# Sheet2.net
KiCad netlist of a schematic drawn in Altium Designer
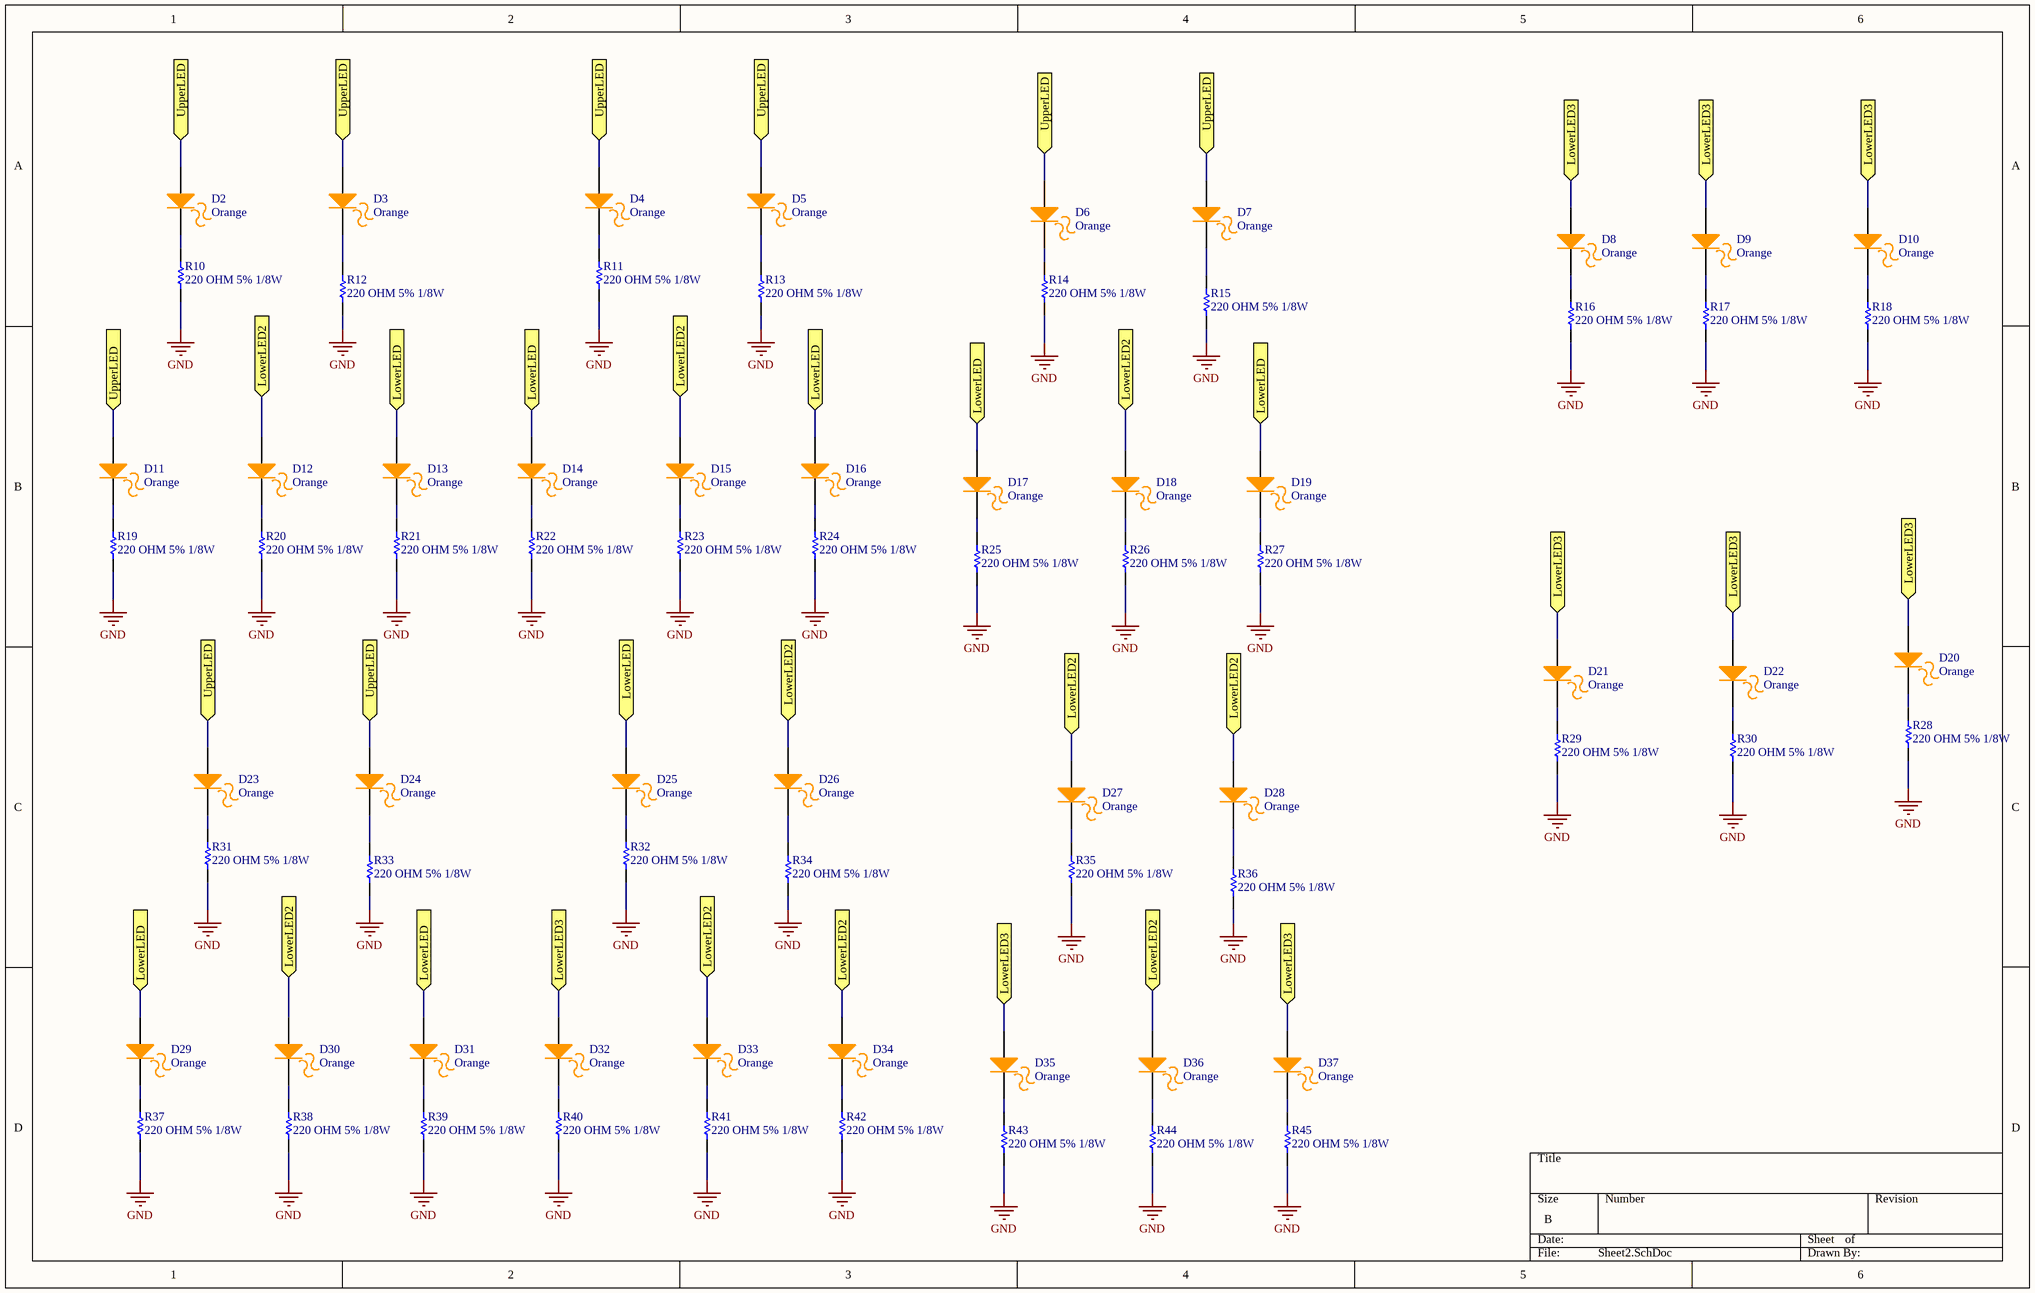
[diagram p0: Sheet2.SchDoc]

(export (version "E")
  (design (tool "Eeschema 10.0.6"))
  (components
    (comp (ref "D2")
      (value "Orange")
      (footprint "0603 LED Green")
      (description "LED ORANGE CLEAR SMD")
      (fields (field (name "MANUFACTURER") "Lite-On Inc."))
      (libsource (lib "CircuitStudioSchematic.Lib") (part "LTST-C191KFKT"))
    )
    (comp (ref "D3")
      (value "Orange")
      (footprint "0603 LED Green")
      (description "LED ORANGE CLEAR SMD")
      (fields (field (name "MANUFACTURER") "Lite-On Inc."))
      (libsource (lib "CircuitStudioSchematic.Lib") (part "LTST-C191KFKT"))
    )
    (comp (ref "D4")
      (value "Orange")
      (footprint "0603 LED Green")
      (description "LED ORANGE CLEAR SMD")
      (fields (field (name "MANUFACTURER") "Lite-On Inc."))
      (libsource (lib "CircuitStudioSchematic.Lib") (part "LTST-C191KFKT"))
    )
    (comp (ref "D5")
      (value "Orange")
      (footprint "0603 LED Green")
      (description "LED ORANGE CLEAR SMD")
      (fields (field (name "MANUFACTURER") "Lite-On Inc."))
      (libsource (lib "CircuitStudioSchematic.Lib") (part "LTST-C191KFKT"))
    )
    (comp (ref "D6")
      (value "Orange")
      (footprint "0603 LED Green")
      (description "LED ORANGE CLEAR SMD")
      (fields (field (name "MANUFACTURER") "Lite-On Inc."))
      (libsource (lib "CircuitStudioSchematic.Lib") (part "LTST-C191KFKT"))
    )
    (comp (ref "D7")
      (value "Orange")
      (footprint "0603 LED Green")
      (description "LED ORANGE CLEAR SMD")
      (fields (field (name "MANUFACTURER") "Lite-On Inc."))
      (libsource (lib "CircuitStudioSchematic.Lib") (part "LTST-C191KFKT"))
    )
    (comp (ref "D8")
      (value "Orange")
      (footprint "0603 LED Green")
      (description "LED ORANGE CLEAR SMD")
      (fields (field (name "MANUFACTURER") "Lite-On Inc."))
      (libsource (lib "CircuitStudioSchematic.Lib") (part "LTST-C191KFKT"))
    )
    (comp (ref "D9")
      (value "Orange")
      (footprint "0603 LED Green")
      (description "LED ORANGE CLEAR SMD")
      (fields (field (name "MANUFACTURER") "Lite-On Inc."))
      (libsource (lib "CircuitStudioSchematic.Lib") (part "LTST-C191KFKT"))
    )
    (comp (ref "D10")
      (value "Orange")
      (footprint "0603 LED Green")
      (description "LED ORANGE CLEAR SMD")
      (fields (field (name "MANUFACTURER") "Lite-On Inc."))
      (libsource (lib "CircuitStudioSchematic.Lib") (part "LTST-C191KFKT"))
    )
    (comp (ref "D11")
      (value "Orange")
      (footprint "0603 LED Green")
      (description "LED ORANGE CLEAR SMD")
      (fields (field (name "MANUFACTURER") "Lite-On Inc."))
      (libsource (lib "CircuitStudioSchematic.Lib") (part "LTST-C191KFKT"))
    )
    (comp (ref "D12")
      (value "Orange")
      (footprint "0603 LED Green")
      (description "LED ORANGE CLEAR SMD")
      (fields (field (name "MANUFACTURER") "Lite-On Inc."))
      (libsource (lib "CircuitStudioSchematic.Lib") (part "LTST-C191KFKT"))
    )
    (comp (ref "D13")
      (value "Orange")
      (footprint "0603 LED Green")
      (description "LED ORANGE CLEAR SMD")
      (fields (field (name "MANUFACTURER") "Lite-On Inc."))
      (libsource (lib "CircuitStudioSchematic.Lib") (part "LTST-C191KFKT"))
    )
    (comp (ref "D14")
      (value "Orange")
      (footprint "0603 LED Green")
      (description "LED ORANGE CLEAR SMD")
      (fields (field (name "MANUFACTURER") "Lite-On Inc."))
      (libsource (lib "CircuitStudioSchematic.Lib") (part "LTST-C191KFKT"))
    )
    (comp (ref "D15")
      (value "Orange")
      (footprint "0603 LED Green")
      (description "LED ORANGE CLEAR SMD")
      (fields (field (name "MANUFACTURER") "Lite-On Inc."))
      (libsource (lib "CircuitStudioSchematic.Lib") (part "LTST-C191KFKT"))
    )
    (comp (ref "D16")
      (value "Orange")
      (footprint "0603 LED Green")
      (description "LED ORANGE CLEAR SMD")
      (fields (field (name "MANUFACTURER") "Lite-On Inc."))
      (libsource (lib "CircuitStudioSchematic.Lib") (part "LTST-C191KFKT"))
    )
    (comp (ref "D17")
      (value "Orange")
      (footprint "0603 LED Green")
      (description "LED ORANGE CLEAR SMD")
      (fields (field (name "MANUFACTURER") "Lite-On Inc."))
      (libsource (lib "CircuitStudioSchematic.Lib") (part "LTST-C191KFKT"))
    )
    (comp (ref "D18")
      (value "Orange")
      (footprint "0603 LED Green")
      (description "LED ORANGE CLEAR SMD")
      (fields (field (name "MANUFACTURER") "Lite-On Inc."))
      (libsource (lib "CircuitStudioSchematic.Lib") (part "LTST-C191KFKT"))
    )
    (comp (ref "D19")
      (value "Orange")
      (footprint "0603 LED Green")
      (description "LED ORANGE CLEAR SMD")
      (fields (field (name "MANUFACTURER") "Lite-On Inc."))
      (libsource (lib "CircuitStudioSchematic.Lib") (part "LTST-C191KFKT"))
    )
    (comp (ref "D20")
      (value "Orange")
      (footprint "0603 LED Green")
      (description "LED ORANGE CLEAR SMD")
      (fields (field (name "MANUFACTURER") "Lite-On Inc."))
      (libsource (lib "CircuitStudioSchematic.Lib") (part "LTST-C191KFKT"))
    )
    (comp (ref "D21")
      (value "Orange")
      (footprint "0603 LED Green")
      (description "LED ORANGE CLEAR SMD")
      (fields (field (name "MANUFACTURER") "Lite-On Inc."))
      (libsource (lib "CircuitStudioSchematic.Lib") (part "LTST-C191KFKT"))
    )
    (comp (ref "D22")
      (value "Orange")
      (footprint "0603 LED Green")
      (description "LED ORANGE CLEAR SMD")
      (fields (field (name "MANUFACTURER") "Lite-On Inc."))
      (libsource (lib "CircuitStudioSchematic.Lib") (part "LTST-C191KFKT"))
    )
    (comp (ref "D23")
      (value "Orange")
      (footprint "0603 LED Green")
      (description "LED ORANGE CLEAR SMD")
      (fields (field (name "MANUFACTURER") "Lite-On Inc."))
      (libsource (lib "CircuitStudioSchematic.Lib") (part "LTST-C191KFKT"))
    )
    (comp (ref "D24")
      (value "Orange")
      (footprint "0603 LED Green")
      (description "LED ORANGE CLEAR SMD")
      (fields (field (name "MANUFACTURER") "Lite-On Inc."))
      (libsource (lib "CircuitStudioSchematic.Lib") (part "LTST-C191KFKT"))
    )
    (comp (ref "D25")
      (value "Orange")
      (footprint "0603 LED Green")
      (description "LED ORANGE CLEAR SMD")
      (fields (field (name "MANUFACTURER") "Lite-On Inc."))
      (libsource (lib "CircuitStudioSchematic.Lib") (part "LTST-C191KFKT"))
    )
    (comp (ref "D26")
      (value "Orange")
      (footprint "0603 LED Green")
      (description "LED ORANGE CLEAR SMD")
      (fields (field (name "MANUFACTURER") "Lite-On Inc."))
      (libsource (lib "CircuitStudioSchematic.Lib") (part "LTST-C191KFKT"))
    )
    (comp (ref "D27")
      (value "Orange")
      (footprint "0603 LED Green")
      (description "LED ORANGE CLEAR SMD")
      (fields (field (name "MANUFACTURER") "Lite-On Inc."))
      (libsource (lib "CircuitStudioSchematic.Lib") (part "LTST-C191KFKT"))
    )
    (comp (ref "D28")
      (value "Orange")
      (footprint "0603 LED Green")
      (description "LED ORANGE CLEAR SMD")
      (fields (field (name "MANUFACTURER") "Lite-On Inc."))
      (libsource (lib "CircuitStudioSchematic.Lib") (part "LTST-C191KFKT"))
    )
    (comp (ref "D29")
      (value "Orange")
      (footprint "0603 LED Green")
      (description "LED ORANGE CLEAR SMD")
      (fields (field (name "MANUFACTURER") "Lite-On Inc."))
      (libsource (lib "CircuitStudioSchematic.Lib") (part "LTST-C191KFKT"))
    )
    (comp (ref "D30")
      (value "Orange")
      (footprint "0603 LED Green")
      (description "LED ORANGE CLEAR SMD")
      (fields (field (name "MANUFACTURER") "Lite-On Inc."))
      (libsource (lib "CircuitStudioSchematic.Lib") (part "LTST-C191KFKT"))
    )
    (comp (ref "D31")
      (value "Orange")
      (footprint "0603 LED Green")
      (description "LED ORANGE CLEAR SMD")
      (fields (field (name "MANUFACTURER") "Lite-On Inc."))
      (libsource (lib "CircuitStudioSchematic.Lib") (part "LTST-C191KFKT"))
    )
    (comp (ref "D32")
      (value "Orange")
      (footprint "0603 LED Green")
      (description "LED ORANGE CLEAR SMD")
      (fields (field (name "MANUFACTURER") "Lite-On Inc."))
      (libsource (lib "CircuitStudioSchematic.Lib") (part "LTST-C191KFKT"))
    )
    (comp (ref "D33")
      (value "Orange")
      (footprint "0603 LED Green")
      (description "LED ORANGE CLEAR SMD")
      (fields (field (name "MANUFACTURER") "Lite-On Inc."))
      (libsource (lib "CircuitStudioSchematic.Lib") (part "LTST-C191KFKT"))
    )
    (comp (ref "D34")
      (value "Orange")
      (footprint "0603 LED Green")
      (description "LED ORANGE CLEAR SMD")
      (fields (field (name "MANUFACTURER") "Lite-On Inc."))
      (libsource (lib "CircuitStudioSchematic.Lib") (part "LTST-C191KFKT"))
    )
    (comp (ref "D35")
      (value "Orange")
      (footprint "0603 LED Green")
      (description "LED ORANGE CLEAR SMD")
      (fields (field (name "MANUFACTURER") "Lite-On Inc."))
      (libsource (lib "CircuitStudioSchematic.Lib") (part "LTST-C191KFKT"))
    )
    (comp (ref "D36")
      (value "Orange")
      (footprint "0603 LED Green")
      (description "LED ORANGE CLEAR SMD")
      (fields (field (name "MANUFACTURER") "Lite-On Inc."))
      (libsource (lib "CircuitStudioSchematic.Lib") (part "LTST-C191KFKT"))
    )
    (comp (ref "D37")
      (value "Orange")
      (footprint "0603 LED Green")
      (description "LED ORANGE CLEAR SMD")
      (fields (field (name "MANUFACTURER") "Lite-On Inc."))
      (libsource (lib "CircuitStudioSchematic.Lib") (part "LTST-C191KFKT"))
    )
    (comp (ref "R10")
      (value "220 OHM 5% 1/8W")
      (footprint "SMD-0805-RES")
      (description "RES SMD 220 OHM 5% 1/8W 0805")
      (fields (field (name "MANUFACTURER") "Yageo"))
      (libsource (lib "CircuitStudioSchematic.Lib") (part "RC0805JR-07220RL"))
    )
    (comp (ref "R11")
      (value "220 OHM 5% 1/8W")
      (footprint "SMD-0805-RES")
      (description "RES SMD 220 OHM 5% 1/8W 0805")
      (fields (field (name "MANUFACTURER") "Yageo"))
      (libsource (lib "CircuitStudioSchematic.Lib") (part "RC0805JR-07220RL"))
    )
    (comp (ref "R12")
      (value "220 OHM 5% 1/8W")
      (footprint "SMD-0805-RES")
      (description "RES SMD 220 OHM 5% 1/8W 0805")
      (fields (field (name "MANUFACTURER") "Yageo"))
      (libsource (lib "CircuitStudioSchematic.Lib") (part "RC0805JR-07220RL"))
    )
    (comp (ref "R13")
      (value "220 OHM 5% 1/8W")
      (footprint "SMD-0805-RES")
      (description "RES SMD 220 OHM 5% 1/8W 0805")
      (fields (field (name "MANUFACTURER") "Yageo"))
      (libsource (lib "CircuitStudioSchematic.Lib") (part "RC0805JR-07220RL"))
    )
    (comp (ref "R14")
      (value "220 OHM 5% 1/8W")
      (footprint "SMD-0805-RES")
      (description "RES SMD 220 OHM 5% 1/8W 0805")
      (fields (field (name "MANUFACTURER") "Yageo"))
      (libsource (lib "CircuitStudioSchematic.Lib") (part "RC0805JR-07220RL"))
    )
    (comp (ref "R15")
      (value "220 OHM 5% 1/8W")
      (footprint "SMD-0805-RES")
      (description "RES SMD 220 OHM 5% 1/8W 0805")
      (fields (field (name "MANUFACTURER") "Yageo"))
      (libsource (lib "CircuitStudioSchematic.Lib") (part "RC0805JR-07220RL"))
    )
    (comp (ref "R16")
      (value "220 OHM 5% 1/8W")
      (footprint "SMD-0805-RES")
      (description "RES SMD 220 OHM 5% 1/8W 0805")
      (fields (field (name "MANUFACTURER") "Yageo"))
      (libsource (lib "CircuitStudioSchematic.Lib") (part "RC0805JR-07220RL"))
    )
    (comp (ref "R17")
      (value "220 OHM 5% 1/8W")
      (footprint "SMD-0805-RES")
      (description "RES SMD 220 OHM 5% 1/8W 0805")
      (fields (field (name "MANUFACTURER") "Yageo"))
      (libsource (lib "CircuitStudioSchematic.Lib") (part "RC0805JR-07220RL"))
    )
    (comp (ref "R18")
      (value "220 OHM 5% 1/8W")
      (footprint "SMD-0805-RES")
      (description "RES SMD 220 OHM 5% 1/8W 0805")
      (fields (field (name "MANUFACTURER") "Yageo"))
      (libsource (lib "CircuitStudioSchematic.Lib") (part "RC0805JR-07220RL"))
    )
    (comp (ref "R19")
      (value "220 OHM 5% 1/8W")
      (footprint "SMD-0805-RES")
      (description "RES SMD 220 OHM 5% 1/8W 0805")
      (fields (field (name "MANUFACTURER") "Yageo"))
      (libsource (lib "CircuitStudioSchematic.Lib") (part "RC0805JR-07220RL"))
    )
    (comp (ref "R20")
      (value "220 OHM 5% 1/8W")
      (footprint "SMD-0805-RES")
      (description "RES SMD 220 OHM 5% 1/8W 0805")
      (fields (field (name "MANUFACTURER") "Yageo"))
      (libsource (lib "CircuitStudioSchematic.Lib") (part "RC0805JR-07220RL"))
    )
    (comp (ref "R21")
      (value "220 OHM 5% 1/8W")
      (footprint "SMD-0805-RES")
      (description "RES SMD 220 OHM 5% 1/8W 0805")
      (fields (field (name "MANUFACTURER") "Yageo"))
      (libsource (lib "CircuitStudioSchematic.Lib") (part "RC0805JR-07220RL"))
    )
    (comp (ref "R22")
      (value "220 OHM 5% 1/8W")
      (footprint "SMD-0805-RES")
      (description "RES SMD 220 OHM 5% 1/8W 0805")
      (fields (field (name "MANUFACTURER") "Yageo"))
      (libsource (lib "CircuitStudioSchematic.Lib") (part "RC0805JR-07220RL"))
    )
    (comp (ref "R23")
      (value "220 OHM 5% 1/8W")
      (footprint "SMD-0805-RES")
      (description "RES SMD 220 OHM 5% 1/8W 0805")
      (fields (field (name "MANUFACTURER") "Yageo"))
      (libsource (lib "CircuitStudioSchematic.Lib") (part "RC0805JR-07220RL"))
    )
    (comp (ref "R24")
      (value "220 OHM 5% 1/8W")
      (footprint "SMD-0805-RES")
      (description "RES SMD 220 OHM 5% 1/8W 0805")
      (fields (field (name "MANUFACTURER") "Yageo"))
      (libsource (lib "CircuitStudioSchematic.Lib") (part "RC0805JR-07220RL"))
    )
    (comp (ref "R25")
      (value "220 OHM 5% 1/8W")
      (footprint "SMD-0805-RES")
      (description "RES SMD 220 OHM 5% 1/8W 0805")
      (fields (field (name "MANUFACTURER") "Yageo"))
      (libsource (lib "CircuitStudioSchematic.Lib") (part "RC0805JR-07220RL"))
    )
    (comp (ref "R26")
      (value "220 OHM 5% 1/8W")
      (footprint "SMD-0805-RES")
      (description "RES SMD 220 OHM 5% 1/8W 0805")
      (fields (field (name "MANUFACTURER") "Yageo"))
      (libsource (lib "CircuitStudioSchematic.Lib") (part "RC0805JR-07220RL"))
    )
    (comp (ref "R27")
      (value "220 OHM 5% 1/8W")
      (footprint "SMD-0805-RES")
      (description "RES SMD 220 OHM 5% 1/8W 0805")
      (fields (field (name "MANUFACTURER") "Yageo"))
      (libsource (lib "CircuitStudioSchematic.Lib") (part "RC0805JR-07220RL"))
    )
    (comp (ref "R28")
      (value "220 OHM 5% 1/8W")
      (footprint "SMD-0805-RES")
      (description "RES SMD 220 OHM 5% 1/8W 0805")
      (fields (field (name "MANUFACTURER") "Yageo"))
      (libsource (lib "CircuitStudioSchematic.Lib") (part "RC0805JR-07220RL"))
    )
    (comp (ref "R29")
      (value "220 OHM 5% 1/8W")
      (footprint "SMD-0805-RES")
      (description "RES SMD 220 OHM 5% 1/8W 0805")
      (fields (field (name "MANUFACTURER") "Yageo"))
      (libsource (lib "CircuitStudioSchematic.Lib") (part "RC0805JR-07220RL"))
    )
    (comp (ref "R30")
      (value "220 OHM 5% 1/8W")
      (footprint "SMD-0805-RES")
      (description "RES SMD 220 OHM 5% 1/8W 0805")
      (fields (field (name "MANUFACTURER") "Yageo"))
      (libsource (lib "CircuitStudioSchematic.Lib") (part "RC0805JR-07220RL"))
    )
    (comp (ref "R31")
      (value "220 OHM 5% 1/8W")
      (footprint "SMD-0805-RES")
      (description "RES SMD 220 OHM 5% 1/8W 0805")
      (fields (field (name "MANUFACTURER") "Yageo"))
      (libsource (lib "CircuitStudioSchematic.Lib") (part "RC0805JR-07220RL"))
    )
    (comp (ref "R32")
      (value "220 OHM 5% 1/8W")
      (footprint "SMD-0805-RES")
      (description "RES SMD 220 OHM 5% 1/8W 0805")
      (fields (field (name "MANUFACTURER") "Yageo"))
      (libsource (lib "CircuitStudioSchematic.Lib") (part "RC0805JR-07220RL"))
    )
    (comp (ref "R33")
      (value "220 OHM 5% 1/8W")
      (footprint "SMD-0805-RES")
      (description "RES SMD 220 OHM 5% 1/8W 0805")
      (fields (field (name "MANUFACTURER") "Yageo"))
      (libsource (lib "CircuitStudioSchematic.Lib") (part "RC0805JR-07220RL"))
    )
    (comp (ref "R34")
      (value "220 OHM 5% 1/8W")
      (footprint "SMD-0805-RES")
      (description "RES SMD 220 OHM 5% 1/8W 0805")
      (fields (field (name "MANUFACTURER") "Yageo"))
      (libsource (lib "CircuitStudioSchematic.Lib") (part "RC0805JR-07220RL"))
    )
    (comp (ref "R35")
      (value "220 OHM 5% 1/8W")
      (footprint "SMD-0805-RES")
      (description "RES SMD 220 OHM 5% 1/8W 0805")
      (fields (field (name "MANUFACTURER") "Yageo"))
      (libsource (lib "CircuitStudioSchematic.Lib") (part "RC0805JR-07220RL"))
    )
    (comp (ref "R36")
      (value "220 OHM 5% 1/8W")
      (footprint "SMD-0805-RES")
      (description "RES SMD 220 OHM 5% 1/8W 0805")
      (fields (field (name "MANUFACTURER") "Yageo"))
      (libsource (lib "CircuitStudioSchematic.Lib") (part "RC0805JR-07220RL"))
    )
    (comp (ref "R37")
      (value "220 OHM 5% 1/8W")
      (footprint "SMD-0805-RES")
      (description "RES SMD 220 OHM 5% 1/8W 0805")
      (fields (field (name "MANUFACTURER") "Yageo"))
      (libsource (lib "CircuitStudioSchematic.Lib") (part "RC0805JR-07220RL"))
    )
    (comp (ref "R38")
      (value "220 OHM 5% 1/8W")
      (footprint "SMD-0805-RES")
      (description "RES SMD 220 OHM 5% 1/8W 0805")
      (fields (field (name "MANUFACTURER") "Yageo"))
      (libsource (lib "CircuitStudioSchematic.Lib") (part "RC0805JR-07220RL"))
    )
    (comp (ref "R39")
      (value "220 OHM 5% 1/8W")
      (footprint "SMD-0805-RES")
      (description "RES SMD 220 OHM 5% 1/8W 0805")
      (fields (field (name "MANUFACTURER") "Yageo"))
      (libsource (lib "CircuitStudioSchematic.Lib") (part "RC0805JR-07220RL"))
    )
    (comp (ref "R40")
      (value "220 OHM 5% 1/8W")
      (footprint "SMD-0805-RES")
      (description "RES SMD 220 OHM 5% 1/8W 0805")
      (fields (field (name "MANUFACTURER") "Yageo"))
      (libsource (lib "CircuitStudioSchematic.Lib") (part "RC0805JR-07220RL"))
    )
    (comp (ref "R41")
      (value "220 OHM 5% 1/8W")
      (footprint "SMD-0805-RES")
      (description "RES SMD 220 OHM 5% 1/8W 0805")
      (fields (field (name "MANUFACTURER") "Yageo"))
      (libsource (lib "CircuitStudioSchematic.Lib") (part "RC0805JR-07220RL"))
    )
    (comp (ref "R42")
      (value "220 OHM 5% 1/8W")
      (footprint "SMD-0805-RES")
      (description "RES SMD 220 OHM 5% 1/8W 0805")
      (fields (field (name "MANUFACTURER") "Yageo"))
      (libsource (lib "CircuitStudioSchematic.Lib") (part "RC0805JR-07220RL"))
    )
    (comp (ref "R43")
      (value "220 OHM 5% 1/8W")
      (footprint "SMD-0805-RES")
      (description "RES SMD 220 OHM 5% 1/8W 0805")
      (fields (field (name "MANUFACTURER") "Yageo"))
      (libsource (lib "CircuitStudioSchematic.Lib") (part "RC0805JR-07220RL"))
    )
    (comp (ref "R44")
      (value "220 OHM 5% 1/8W")
      (footprint "SMD-0805-RES")
      (description "RES SMD 220 OHM 5% 1/8W 0805")
      (fields (field (name "MANUFACTURER") "Yageo"))
      (libsource (lib "CircuitStudioSchematic.Lib") (part "RC0805JR-07220RL"))
    )
    (comp (ref "R45")
      (value "220 OHM 5% 1/8W")
      (footprint "SMD-0805-RES")
      (description "RES SMD 220 OHM 5% 1/8W 0805")
      (fields (field (name "MANUFACTURER") "Yageo"))
      (libsource (lib "CircuitStudioSchematic.Lib") (part "RC0805JR-07220RL"))
    )
  )
  (nets
    (net (code "1") (name "/LowerLED") (class "Default")
      (node (ref "D13") (pin "1") (pinfunction "Anode_1") (pintype "passive"))
      (node (ref "D14") (pin "1") (pinfunction "Anode_1") (pintype "passive"))
      (node (ref "D16") (pin "1") (pinfunction "Anode_1") (pintype "passive"))
      (node (ref "D17") (pin "1") (pinfunction "Anode_1") (pintype "passive"))
      (node (ref "D19") (pin "1") (pinfunction "Anode_1") (pintype "passive"))
      (node (ref "D25") (pin "1") (pinfunction "Anode_1") (pintype "passive"))
      (node (ref "D29") (pin "1") (pinfunction "Anode_1") (pintype "passive"))
      (node (ref "D31") (pin "1") (pinfunction "Anode_1") (pintype "passive"))
    )
    (net (code "2") (name "/LowerLED2") (class "Default")
      (node (ref "D12") (pin "1") (pinfunction "Anode_1") (pintype "passive"))
      (node (ref "D15") (pin "1") (pinfunction "Anode_1") (pintype "passive"))
      (node (ref "D18") (pin "1") (pinfunction "Anode_1") (pintype "passive"))
      (node (ref "D26") (pin "1") (pinfunction "Anode_1") (pintype "passive"))
      (node (ref "D27") (pin "1") (pinfunction "Anode_1") (pintype "passive"))
      (node (ref "D28") (pin "1") (pinfunction "Anode_1") (pintype "passive"))
      (node (ref "D30") (pin "1") (pinfunction "Anode_1") (pintype "passive"))
      (node (ref "D33") (pin "1") (pinfunction "Anode_1") (pintype "passive"))
      (node (ref "D34") (pin "1") (pinfunction "Anode_1") (pintype "passive"))
      (node (ref "D36") (pin "1") (pinfunction "Anode_1") (pintype "passive"))
    )
    (net (code "3") (name "/LowerLED3") (class "Default")
      (node (ref "D10") (pin "1") (pinfunction "Anode_1") (pintype "passive"))
      (node (ref "D20") (pin "1") (pinfunction "Anode_1") (pintype "passive"))
      (node (ref "D21") (pin "1") (pinfunction "Anode_1") (pintype "passive"))
      (node (ref "D22") (pin "1") (pinfunction "Anode_1") (pintype "passive"))
      (node (ref "D32") (pin "1") (pinfunction "Anode_1") (pintype "passive"))
      (node (ref "D35") (pin "1") (pinfunction "Anode_1") (pintype "passive"))
      (node (ref "D37") (pin "1") (pinfunction "Anode_1") (pintype "passive"))
      (node (ref "D8") (pin "1") (pinfunction "Anode_1") (pintype "passive"))
      (node (ref "D9") (pin "1") (pinfunction "Anode_1") (pintype "passive"))
    )
    (net (code "4") (name "/UpperLED") (class "Default")
      (node (ref "D11") (pin "1") (pinfunction "Anode_1") (pintype "passive"))
      (node (ref "D2") (pin "1") (pinfunction "Anode_1") (pintype "passive"))
      (node (ref "D23") (pin "1") (pinfunction "Anode_1") (pintype "passive"))
      (node (ref "D24") (pin "1") (pinfunction "Anode_1") (pintype "passive"))
      (node (ref "D3") (pin "1") (pinfunction "Anode_1") (pintype "passive"))
      (node (ref "D4") (pin "1") (pinfunction "Anode_1") (pintype "passive"))
      (node (ref "D5") (pin "1") (pinfunction "Anode_1") (pintype "passive"))
      (node (ref "D6") (pin "1") (pinfunction "Anode_1") (pintype "passive"))
      (node (ref "D7") (pin "1") (pinfunction "Anode_1") (pintype "passive"))
    )
    (net (code "5") (name "GND") (class "Default")
      (node (ref "R10") (pin "1") (pinfunction "1_1") (pintype "passive"))
      (node (ref "R11") (pin "1") (pinfunction "1_1") (pintype "passive"))
      (node (ref "R12") (pin "1") (pinfunction "1_1") (pintype "passive"))
      (node (ref "R13") (pin "1") (pinfunction "1_1") (pintype "passive"))
      (node (ref "R14") (pin "1") (pinfunction "1_1") (pintype "passive"))
      (node (ref "R15") (pin "1") (pinfunction "1_1") (pintype "passive"))
      (node (ref "R16") (pin "1") (pinfunction "1_1") (pintype "passive"))
      (node (ref "R17") (pin "1") (pinfunction "1_1") (pintype "passive"))
      (node (ref "R18") (pin "1") (pinfunction "1_1") (pintype "passive"))
      (node (ref "R19") (pin "1") (pinfunction "1_1") (pintype "passive"))
      (node (ref "R20") (pin "1") (pinfunction "1_1") (pintype "passive"))
      (node (ref "R21") (pin "1") (pinfunction "1_1") (pintype "passive"))
      (node (ref "R22") (pin "1") (pinfunction "1_1") (pintype "passive"))
      (node (ref "R23") (pin "1") (pinfunction "1_1") (pintype "passive"))
      (node (ref "R24") (pin "1") (pinfunction "1_1") (pintype "passive"))
      (node (ref "R25") (pin "1") (pinfunction "1_1") (pintype "passive"))
      (node (ref "R26") (pin "1") (pinfunction "1_1") (pintype "passive"))
      (node (ref "R27") (pin "1") (pinfunction "1_1") (pintype "passive"))
      (node (ref "R28") (pin "1") (pinfunction "1_1") (pintype "passive"))
      (node (ref "R29") (pin "1") (pinfunction "1_1") (pintype "passive"))
      (node (ref "R30") (pin "1") (pinfunction "1_1") (pintype "passive"))
      (node (ref "R31") (pin "1") (pinfunction "1_1") (pintype "passive"))
      (node (ref "R32") (pin "1") (pinfunction "1_1") (pintype "passive"))
      (node (ref "R33") (pin "1") (pinfunction "1_1") (pintype "passive"))
      (node (ref "R34") (pin "1") (pinfunction "1_1") (pintype "passive"))
      (node (ref "R35") (pin "1") (pinfunction "1_1") (pintype "passive"))
      (node (ref "R36") (pin "1") (pinfunction "1_1") (pintype "passive"))
      (node (ref "R37") (pin "1") (pinfunction "1_1") (pintype "passive"))
      (node (ref "R38") (pin "1") (pinfunction "1_1") (pintype "passive"))
      (node (ref "R39") (pin "1") (pinfunction "1_1") (pintype "passive"))
      (node (ref "R40") (pin "1") (pinfunction "1_1") (pintype "passive"))
      (node (ref "R41") (pin "1") (pinfunction "1_1") (pintype "passive"))
      (node (ref "R42") (pin "1") (pinfunction "1_1") (pintype "passive"))
      (node (ref "R43") (pin "1") (pinfunction "1_1") (pintype "passive"))
      (node (ref "R44") (pin "1") (pinfunction "1_1") (pintype "passive"))
      (node (ref "R45") (pin "1") (pinfunction "1_1") (pintype "passive"))
    )
    (net (code "6") (name "Net-(D2-Cathode)") (class "Default")
      (node (ref "D2") (pin "2") (pinfunction "Cathode_2") (pintype "passive"))
      (node (ref "R10") (pin "2") (pinfunction "2_2") (pintype "passive"))
    )
    (net (code "7") (name "Net-(D3-Cathode)") (class "Default")
      (node (ref "D3") (pin "2") (pinfunction "Cathode_2") (pintype "passive"))
      (node (ref "R12") (pin "2") (pinfunction "2_2") (pintype "passive"))
    )
    (net (code "8") (name "Net-(D4-Cathode)") (class "Default")
      (node (ref "D4") (pin "2") (pinfunction "Cathode_2") (pintype "passive"))
      (node (ref "R11") (pin "2") (pinfunction "2_2") (pintype "passive"))
    )
    (net (code "9") (name "Net-(D5-Cathode)") (class "Default")
      (node (ref "D5") (pin "2") (pinfunction "Cathode_2") (pintype "passive"))
      (node (ref "R13") (pin "2") (pinfunction "2_2") (pintype "passive"))
    )
    (net (code "10") (name "Net-(D6-Cathode)") (class "Default")
      (node (ref "D6") (pin "2") (pinfunction "Cathode_2") (pintype "passive"))
      (node (ref "R14") (pin "2") (pinfunction "2_2") (pintype "passive"))
    )
    (net (code "11") (name "Net-(D7-Cathode)") (class "Default")
      (node (ref "D7") (pin "2") (pinfunction "Cathode_2") (pintype "passive"))
      (node (ref "R15") (pin "2") (pinfunction "2_2") (pintype "passive"))
    )
    (net (code "12") (name "Net-(D8-Cathode)") (class "Default")
      (node (ref "D8") (pin "2") (pinfunction "Cathode_2") (pintype "passive"))
      (node (ref "R16") (pin "2") (pinfunction "2_2") (pintype "passive"))
    )
    (net (code "13") (name "Net-(D9-Cathode)") (class "Default")
      (node (ref "D9") (pin "2") (pinfunction "Cathode_2") (pintype "passive"))
      (node (ref "R17") (pin "2") (pinfunction "2_2") (pintype "passive"))
    )
    (net (code "14") (name "Net-(D10-Cathode)") (class "Default")
      (node (ref "D10") (pin "2") (pinfunction "Cathode_2") (pintype "passive"))
      (node (ref "R18") (pin "2") (pinfunction "2_2") (pintype "passive"))
    )
    (net (code "15") (name "Net-(D11-Cathode)") (class "Default")
      (node (ref "D11") (pin "2") (pinfunction "Cathode_2") (pintype "passive"))
      (node (ref "R19") (pin "2") (pinfunction "2_2") (pintype "passive"))
    )
    (net (code "16") (name "Net-(D12-Cathode)") (class "Default")
      (node (ref "D12") (pin "2") (pinfunction "Cathode_2") (pintype "passive"))
      (node (ref "R20") (pin "2") (pinfunction "2_2") (pintype "passive"))
    )
    (net (code "17") (name "Net-(D13-Cathode)") (class "Default")
      (node (ref "D13") (pin "2") (pinfunction "Cathode_2") (pintype "passive"))
      (node (ref "R21") (pin "2") (pinfunction "2_2") (pintype "passive"))
    )
    (net (code "18") (name "Net-(D14-Cathode)") (class "Default")
      (node (ref "D14") (pin "2") (pinfunction "Cathode_2") (pintype "passive"))
      (node (ref "R22") (pin "2") (pinfunction "2_2") (pintype "passive"))
    )
    (net (code "19") (name "Net-(D15-Cathode)") (class "Default")
      (node (ref "D15") (pin "2") (pinfunction "Cathode_2") (pintype "passive"))
      (node (ref "R23") (pin "2") (pinfunction "2_2") (pintype "passive"))
    )
    (net (code "20") (name "Net-(D16-Cathode)") (class "Default")
      (node (ref "D16") (pin "2") (pinfunction "Cathode_2") (pintype "passive"))
      (node (ref "R24") (pin "2") (pinfunction "2_2") (pintype "passive"))
    )
    (net (code "21") (name "Net-(D17-Cathode)") (class "Default")
      (node (ref "D17") (pin "2") (pinfunction "Cathode_2") (pintype "passive"))
      (node (ref "R25") (pin "2") (pinfunction "2_2") (pintype "passive"))
    )
    (net (code "22") (name "Net-(D18-Cathode)") (class "Default")
      (node (ref "D18") (pin "2") (pinfunction "Cathode_2") (pintype "passive"))
      (node (ref "R26") (pin "2") (pinfunction "2_2") (pintype "passive"))
    )
    (net (code "23") (name "Net-(D19-Cathode)") (class "Default")
      (node (ref "D19") (pin "2") (pinfunction "Cathode_2") (pintype "passive"))
      (node (ref "R27") (pin "2") (pinfunction "2_2") (pintype "passive"))
    )
    (net (code "24") (name "Net-(D20-Cathode)") (class "Default")
      (node (ref "D20") (pin "2") (pinfunction "Cathode_2") (pintype "passive"))
      (node (ref "R28") (pin "2") (pinfunction "2_2") (pintype "passive"))
    )
    (net (code "25") (name "Net-(D21-Cathode)") (class "Default")
      (node (ref "D21") (pin "2") (pinfunction "Cathode_2") (pintype "passive"))
      (node (ref "R29") (pin "2") (pinfunction "2_2") (pintype "passive"))
    )
    (net (code "26") (name "Net-(D22-Cathode)") (class "Default")
      (node (ref "D22") (pin "2") (pinfunction "Cathode_2") (pintype "passive"))
      (node (ref "R30") (pin "2") (pinfunction "2_2") (pintype "passive"))
    )
    (net (code "27") (name "Net-(D23-Cathode)") (class "Default")
      (node (ref "D23") (pin "2") (pinfunction "Cathode_2") (pintype "passive"))
      (node (ref "R31") (pin "2") (pinfunction "2_2") (pintype "passive"))
    )
    (net (code "28") (name "Net-(D24-Cathode)") (class "Default")
      (node (ref "D24") (pin "2") (pinfunction "Cathode_2") (pintype "passive"))
      (node (ref "R33") (pin "2") (pinfunction "2_2") (pintype "passive"))
    )
    (net (code "29") (name "Net-(D25-Cathode)") (class "Default")
      (node (ref "D25") (pin "2") (pinfunction "Cathode_2") (pintype "passive"))
      (node (ref "R32") (pin "2") (pinfunction "2_2") (pintype "passive"))
    )
    (net (code "30") (name "Net-(D26-Cathode)") (class "Default")
      (node (ref "D26") (pin "2") (pinfunction "Cathode_2") (pintype "passive"))
      (node (ref "R34") (pin "2") (pinfunction "2_2") (pintype "passive"))
    )
    (net (code "31") (name "Net-(D27-Cathode)") (class "Default")
      (node (ref "D27") (pin "2") (pinfunction "Cathode_2") (pintype "passive"))
      (node (ref "R35") (pin "2") (pinfunction "2_2") (pintype "passive"))
    )
    (net (code "32") (name "Net-(D28-Cathode)") (class "Default")
      (node (ref "D28") (pin "2") (pinfunction "Cathode_2") (pintype "passive"))
      (node (ref "R36") (pin "2") (pinfunction "2_2") (pintype "passive"))
    )
    (net (code "33") (name "Net-(D29-Cathode)") (class "Default")
      (node (ref "D29") (pin "2") (pinfunction "Cathode_2") (pintype "passive"))
      (node (ref "R37") (pin "2") (pinfunction "2_2") (pintype "passive"))
    )
    (net (code "34") (name "Net-(D30-Cathode)") (class "Default")
      (node (ref "D30") (pin "2") (pinfunction "Cathode_2") (pintype "passive"))
      (node (ref "R38") (pin "2") (pinfunction "2_2") (pintype "passive"))
    )
    (net (code "35") (name "Net-(D31-Cathode)") (class "Default")
      (node (ref "D31") (pin "2") (pinfunction "Cathode_2") (pintype "passive"))
      (node (ref "R39") (pin "2") (pinfunction "2_2") (pintype "passive"))
    )
    (net (code "36") (name "Net-(D32-Cathode)") (class "Default")
      (node (ref "D32") (pin "2") (pinfunction "Cathode_2") (pintype "passive"))
      (node (ref "R40") (pin "2") (pinfunction "2_2") (pintype "passive"))
    )
    (net (code "37") (name "Net-(D33-Cathode)") (class "Default")
      (node (ref "D33") (pin "2") (pinfunction "Cathode_2") (pintype "passive"))
      (node (ref "R41") (pin "2") (pinfunction "2_2") (pintype "passive"))
    )
    (net (code "38") (name "Net-(D34-Cathode)") (class "Default")
      (node (ref "D34") (pin "2") (pinfunction "Cathode_2") (pintype "passive"))
      (node (ref "R42") (pin "2") (pinfunction "2_2") (pintype "passive"))
    )
    (net (code "39") (name "Net-(D35-Cathode)") (class "Default")
      (node (ref "D35") (pin "2") (pinfunction "Cathode_2") (pintype "passive"))
      (node (ref "R43") (pin "2") (pinfunction "2_2") (pintype "passive"))
    )
    (net (code "40") (name "Net-(D36-Cathode)") (class "Default")
      (node (ref "D36") (pin "2") (pinfunction "Cathode_2") (pintype "passive"))
      (node (ref "R44") (pin "2") (pinfunction "2_2") (pintype "passive"))
    )
    (net (code "41") (name "Net-(D37-Cathode)") (class "Default")
      (node (ref "D37") (pin "2") (pinfunction "Cathode_2") (pintype "passive"))
      (node (ref "R45") (pin "2") (pinfunction "2_2") (pintype "passive"))
    )
  )
)
